# QED_2550_SOLO.net
KiCad netlist of a schematic drawn in EAGLE
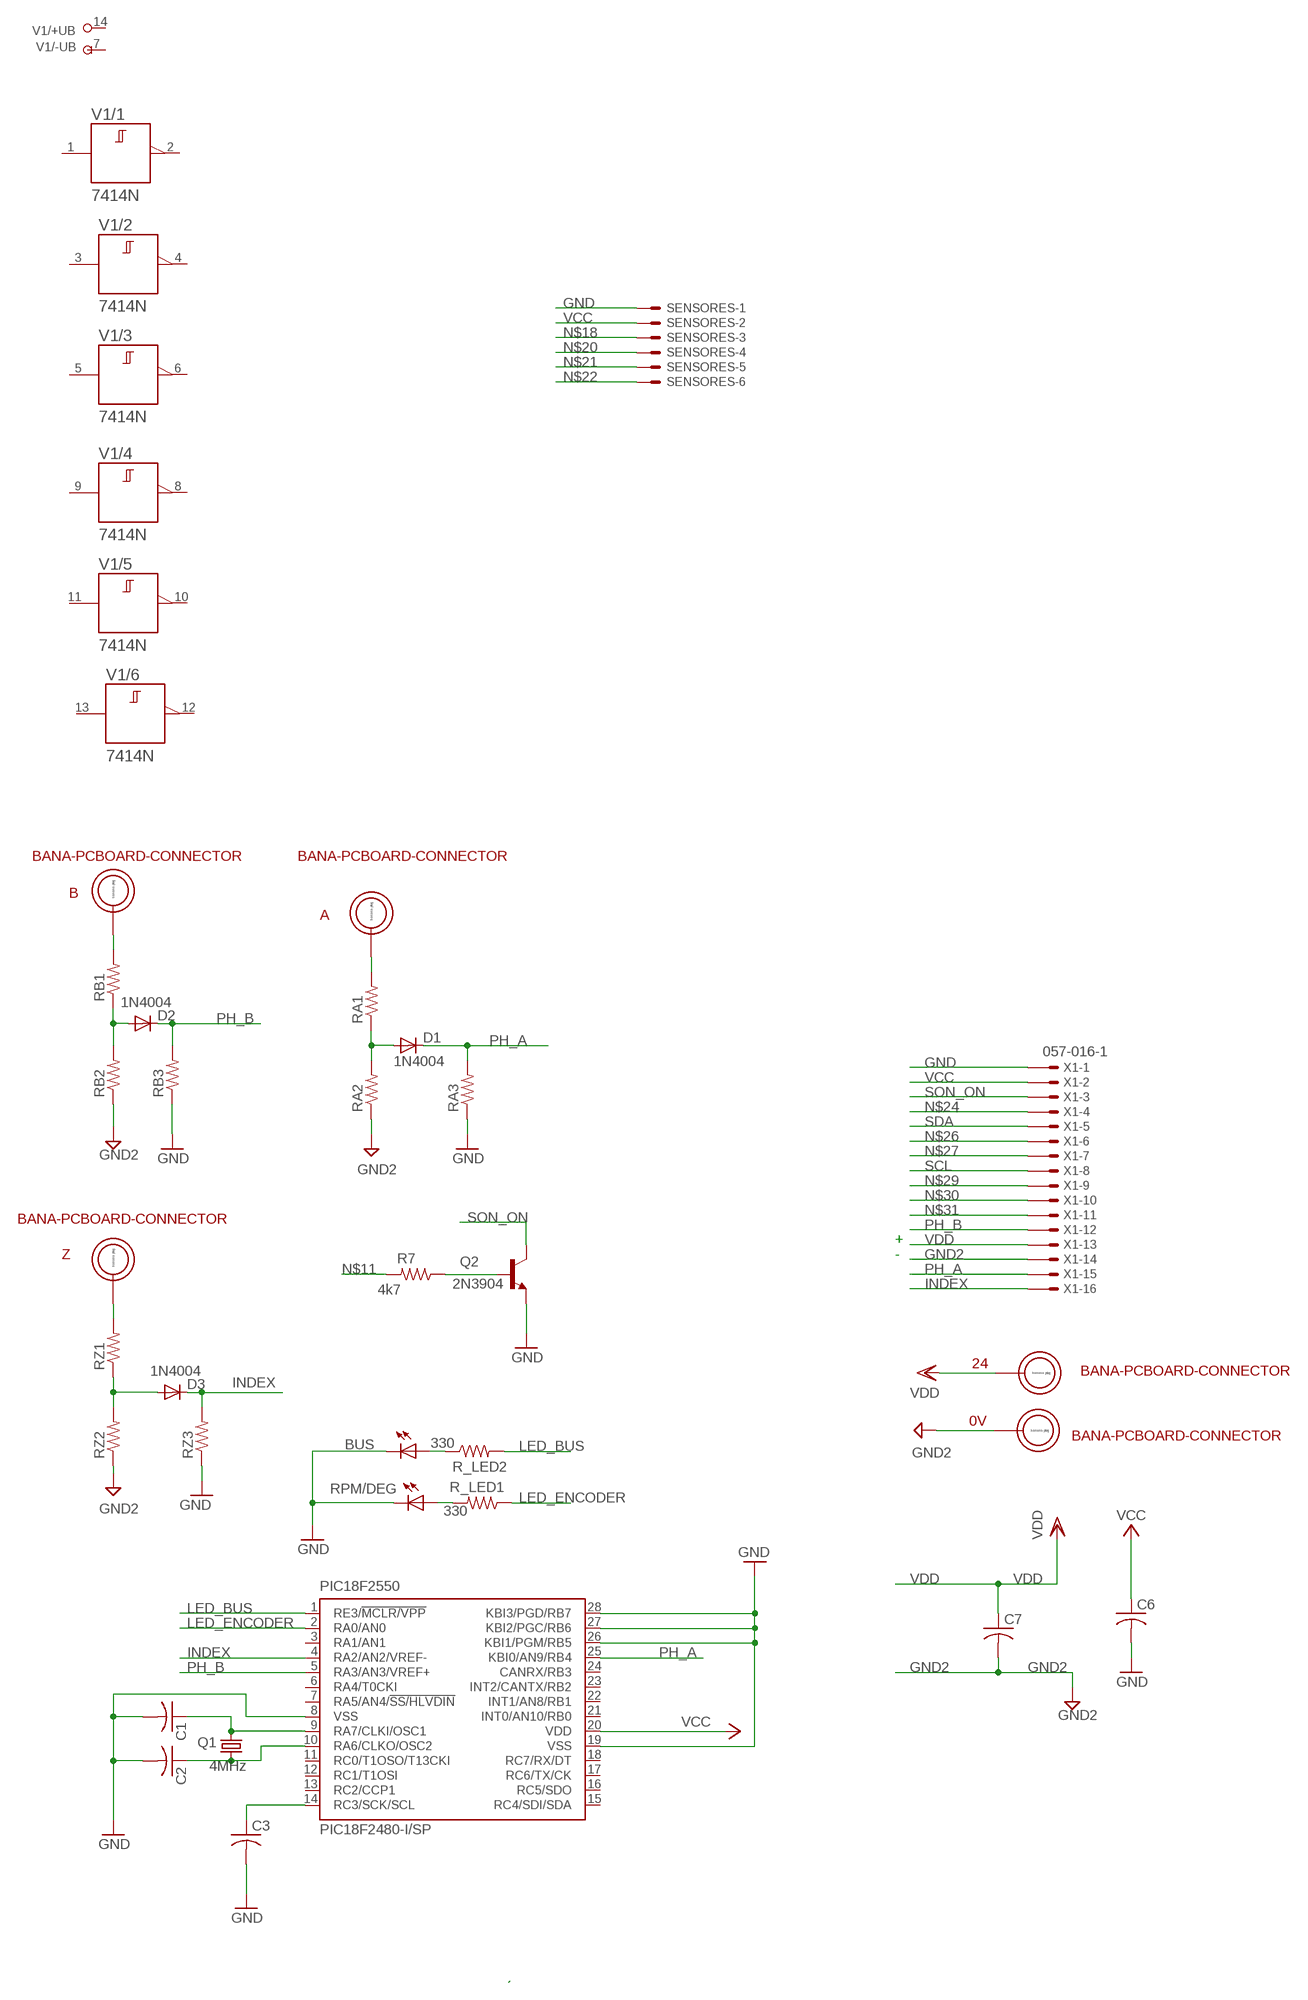
[diagram p0: schematic, sheet 1]

(export (version "E")
  (design (tool "Eeschema 10.0.6"))
  (components
    (comp (ref "0V")
      (value "BANA-PCBOARD-CONNECTOR")
      (footprint "eagle-import:BANA_PLUG")
      (libsource (lib "eagle-import") (part "BANA-PCBOARD-CONNECTOR"))
    )
    (comp (ref "24")
      (value "BANA-PCBOARD-CONNECTOR")
      (footprint "eagle-import:BANA_PLUG")
      (libsource (lib "eagle-import") (part "BANA-PCBOARD-CONNECTOR"))
    )
    (comp (ref "A")
      (value "BANA-PCBOARD-CONNECTOR")
      (footprint "eagle-import:BANA_PLUG")
      (libsource (lib "eagle-import") (part "BANA-PCBOARD-CONNECTOR"))
    )
    (comp (ref "B")
      (value "BANA-PCBOARD-CONNECTOR")
      (footprint "eagle-import:BANA_PLUG")
      (libsource (lib "eagle-import") (part "BANA-PCBOARD-CONNECTOR"))
    )
    (comp (ref "BUS")
      (value "LED5MM")
      (footprint "eagle-import:LED5MM")
      (libsource (lib "eagle-import") (part "LED5MM"))
    )
    (comp (ref "C1")
      (value "C-US025-024X044")
      (footprint "eagle-import:C025-024X044")
      (libsource (lib "eagle-import") (part "C-US025-024X044"))
    )
    (comp (ref "C2")
      (value "C-US025-024X044")
      (footprint "eagle-import:C025-024X044")
      (libsource (lib "eagle-import") (part "C-US025-024X044"))
    )
    (comp (ref "C3")
      (value "C-US025-024X044")
      (footprint "eagle-import:C025-024X044")
      (libsource (lib "eagle-import") (part "C-US025-024X044"))
    )
    (comp (ref "C6")
      (value "C-US025-030X050")
      (footprint "eagle-import:C025-030X050")
      (libsource (lib "eagle-import") (part "C-US025-030X050"))
    )
    (comp (ref "C7")
      (value "C-US025-030X050")
      (footprint "eagle-import:C025-030X050")
      (libsource (lib "eagle-import") (part "C-US025-030X050"))
    )
    (comp (ref "D1")
      (value "1N4004")
      (footprint "eagle-import:DO41-10")
      (libsource (lib "eagle-import") (part "1N4004"))
    )
    (comp (ref "D2")
      (value "1N4004")
      (footprint "eagle-import:DO41-10")
      (libsource (lib "eagle-import") (part "1N4004"))
    )
    (comp (ref "D3")
      (value "1N4004")
      (footprint "eagle-import:DO41-10")
      (libsource (lib "eagle-import") (part "1N4004"))
    )
    (comp (ref "PIC18F2550")
      (value "PIC18F2480-I/SP")
      (footprint "eagle-import:DIL28-3")
      (fields (field (name "MF") "MICROCHIP"))
      (libsource (lib "eagle-import") (part "PIC18F280-I/SP4"))
    )
    (comp (ref "Q1")
      (value "4MHz")
      (footprint "eagle-import:HC49_S")
      (libsource (lib "eagle-import") (part "CRYSTALHC49S"))
    )
    (comp (ref "Q2")
      (value "2N3904")
      (footprint "eagle-import:TO92")
      (libsource (lib "eagle-import") (part "2N3904"))
    )
    (comp (ref "R7")
      (value "4k7")
      (footprint "eagle-import:0204_7")
      (libsource (lib "eagle-import") (part "R-US_0204/7"))
    )
    (comp (ref "RA1")
      (value "R-US_0204/7")
      (footprint "eagle-import:0204_7")
      (libsource (lib "eagle-import") (part "R-US_0204/7"))
    )
    (comp (ref "RA2")
      (value "R-US_0204/7")
      (footprint "eagle-import:0204_7")
      (libsource (lib "eagle-import") (part "R-US_0204/7"))
    )
    (comp (ref "RA3")
      (value "R-US_0204/7")
      (footprint "eagle-import:0204_7")
      (libsource (lib "eagle-import") (part "R-US_0204/7"))
    )
    (comp (ref "RB1")
      (value "R-US_0204/7")
      (footprint "eagle-import:0204_7")
      (libsource (lib "eagle-import") (part "R-US_0204/7"))
    )
    (comp (ref "RB2")
      (value "R-US_0204/7")
      (footprint "eagle-import:0204_7")
      (libsource (lib "eagle-import") (part "R-US_0204/7"))
    )
    (comp (ref "RB3")
      (value "R-US_0204/7")
      (footprint "eagle-import:0204_7")
      (libsource (lib "eagle-import") (part "R-US_0204/7"))
    )
    (comp (ref "RPM/DEG")
      (value "LED5MM")
      (footprint "eagle-import:LED5MM")
      (libsource (lib "eagle-import") (part "LED5MM"))
    )
    (comp (ref "RZ1")
      (value "R-US_0204/7")
      (footprint "eagle-import:0204_7")
      (libsource (lib "eagle-import") (part "R-US_0204/7"))
    )
    (comp (ref "RZ2")
      (value "R-US_0204/7")
      (footprint "eagle-import:0204_7")
      (libsource (lib "eagle-import") (part "R-US_0204/7"))
    )
    (comp (ref "RZ3")
      (value "R-US_0204/7")
      (footprint "eagle-import:0204_7")
      (libsource (lib "eagle-import") (part "R-US_0204/7"))
    )
    (comp (ref "R_LED1")
      (value "330")
      (footprint "eagle-import:0204_7")
      (libsource (lib "eagle-import") (part "R-US_0204/7"))
    )
    (comp (ref "R_LED2")
      (value "330")
      (footprint "eagle-import:0204_7")
      (libsource (lib "eagle-import") (part "R-US_0204/7"))
    )
    (comp (ref "SENSORES")
      (value "22-23-2061")
      (footprint "eagle-import:22-23-2061")
      (fields (field (name "MF") "MOLEX"))
      (libsource (lib "eagle-import") (part "22-23-2061"))
    )
    (comp (ref "V1")
      (value "7414N")
      (footprint "eagle-import:DIL14")
      (libsource (lib "eagle-import") (part "7414N"))
    )
    (comp (ref "X1")
      (value "057-016-1")
      (footprint "eagle-import:057-016-1")
      (libsource (lib "eagle-import") (part "057-016-1"))
    )
    (comp (ref "Z")
      (value "BANA-PCBOARD-CONNECTOR")
      (footprint "eagle-import:BANA_PLUG")
      (libsource (lib "eagle-import") (part "BANA-PCBOARD-CONNECTOR"))
    )
  )
  (nets
    (net (code "1") (name "/+UB") (class "Default")
      (node (ref "V1") (pin "14") (pinfunction "+UB_14") (pintype "power_in"))
    )
    (net (code "2") (name "/-UB") (class "Default")
      (node (ref "V1") (pin "7") (pinfunction "-UB_7") (pintype "power_in"))
    )
    (net (code "3") (name "/INDEX") (class "Default")
      (node (ref "D3") (pin "C") (pinfunction "C_C") (pintype "passive"))
      (node (ref "PIC18F2550") (pin "4") (pinfunction "RA2/AN2/VREF-_4") (pintype "bidirectional"))
      (node (ref "RZ3") (pin "2") (pinfunction "2_2") (pintype "passive"))
      (node (ref "X1") (pin "16") (pinfunction "S_16") (pintype "passive"))
    )
    (net (code "4") (name "/LED_BUS") (class "Default")
      (node (ref "PIC18F2550") (pin "1") (pinfunction "RE3/~{MCLR/VPP}_1") (pintype "input"))
      (node (ref "R_LED2") (pin "2") (pinfunction "2_2") (pintype "passive"))
    )
    (net (code "5") (name "/LED_ENCODER") (class "Default")
      (node (ref "PIC18F2550") (pin "2") (pinfunction "RA0/AN0_2") (pintype "bidirectional"))
      (node (ref "R_LED1") (pin "1") (pinfunction "1_1") (pintype "passive"))
    )
    (net (code "6") (name "/N$11") (class "Default")
      (node (ref "R7") (pin "2") (pinfunction "2_2") (pintype "passive"))
    )
    (net (code "7") (name "/N$18") (class "Default")
      (node (ref "SENSORES") (pin "3") (pinfunction "S_3") (pintype "passive"))
    )
    (net (code "8") (name "/N$20") (class "Default")
      (node (ref "SENSORES") (pin "4") (pinfunction "S_4") (pintype "passive"))
    )
    (net (code "9") (name "/N$21") (class "Default")
      (node (ref "SENSORES") (pin "5") (pinfunction "S_5") (pintype "passive"))
    )
    (net (code "10") (name "/N$22") (class "Default")
      (node (ref "SENSORES") (pin "6") (pinfunction "S_6") (pintype "passive"))
    )
    (net (code "11") (name "/N$24") (class "Default")
      (node (ref "X1") (pin "4") (pinfunction "S_4") (pintype "passive"))
    )
    (net (code "12") (name "/N$26") (class "Default")
      (node (ref "X1") (pin "6") (pinfunction "S_6") (pintype "passive"))
    )
    (net (code "13") (name "/N$27") (class "Default")
      (node (ref "X1") (pin "7") (pinfunction "S_7") (pintype "passive"))
    )
    (net (code "14") (name "/N$29") (class "Default")
      (node (ref "X1") (pin "9") (pinfunction "S_9") (pintype "passive"))
    )
    (net (code "15") (name "/N$30") (class "Default")
      (node (ref "X1") (pin "10") (pinfunction "S_10") (pintype "passive"))
    )
    (net (code "16") (name "/N$31") (class "Default")
      (node (ref "X1") (pin "11") (pinfunction "S_11") (pintype "passive"))
    )
    (net (code "17") (name "/PH_A") (class "Default")
      (node (ref "D1") (pin "C") (pinfunction "C_C") (pintype "passive"))
      (node (ref "PIC18F2550") (pin "25") (pinfunction "KBI0/AN9/RB4_25") (pintype "bidirectional"))
      (node (ref "RA3") (pin "2") (pinfunction "2_2") (pintype "passive"))
      (node (ref "X1") (pin "15") (pinfunction "S_15") (pintype "passive"))
    )
    (net (code "18") (name "/PH_B") (class "Default")
      (node (ref "D2") (pin "C") (pinfunction "C_C") (pintype "passive"))
      (node (ref "PIC18F2550") (pin "5") (pinfunction "RA3/AN3/VREF+_5") (pintype "bidirectional"))
      (node (ref "RB3") (pin "2") (pinfunction "2_2") (pintype "passive"))
      (node (ref "X1") (pin "12") (pinfunction "S_12") (pintype "passive"))
    )
    (net (code "19") (name "/SCL") (class "Default")
      (node (ref "X1") (pin "8") (pinfunction "S_8") (pintype "passive"))
    )
    (net (code "20") (name "/SDA") (class "Default")
      (node (ref "X1") (pin "5") (pinfunction "S_5") (pintype "passive"))
    )
    (net (code "21") (name "/SON_ON") (class "Default")
      (node (ref "Q2") (pin "1") (pinfunction "C_1") (pintype "passive"))
      (node (ref "X1") (pin "3") (pinfunction "S_3") (pintype "passive"))
    )
    (net (code "22") (name "GND") (class "Default")
      (node (ref "BUS") (pin "K") (pinfunction "C_K") (pintype "passive"))
      (node (ref "C1") (pin "2") (pinfunction "2_2") (pintype "passive"))
      (node (ref "C2") (pin "2") (pinfunction "2_2") (pintype "passive"))
      (node (ref "C3") (pin "2") (pinfunction "2_2") (pintype "passive"))
      (node (ref "C6") (pin "2") (pinfunction "2_2") (pintype "passive"))
      (node (ref "PIC18F2550") (pin "19") (pinfunction "VSS_19") (pintype "power_in"))
      (node (ref "PIC18F2550") (pin "26") (pinfunction "KBI1/PGM/RB5_26") (pintype "bidirectional"))
      (node (ref "PIC18F2550") (pin "27") (pinfunction "KBI2/PGC/RB6_27") (pintype "bidirectional"))
      (node (ref "PIC18F2550") (pin "28") (pinfunction "KBI3/PGD/RB7_28") (pintype "bidirectional"))
      (node (ref "PIC18F2550") (pin "8") (pinfunction "VSS_8") (pintype "power_in"))
      (node (ref "Q2") (pin "3") (pinfunction "E_3") (pintype "passive"))
      (node (ref "RA3") (pin "1") (pinfunction "1_1") (pintype "passive"))
      (node (ref "RB3") (pin "1") (pinfunction "1_1") (pintype "passive"))
      (node (ref "RPM/DEG") (pin "K") (pinfunction "C_K") (pintype "passive"))
      (node (ref "RZ3") (pin "1") (pinfunction "1_1") (pintype "passive"))
      (node (ref "SENSORES") (pin "1") (pinfunction "S_1") (pintype "passive"))
      (node (ref "X1") (pin "1") (pinfunction "S_1") (pintype "passive"))
    )
    (net (code "23") (name "GND2") (class "Default")
      (node (ref "0V") (pin "P$1") (pinfunction "P$1_P$1") (pintype "bidirectional"))
      (node (ref "C7") (pin "2") (pinfunction "2_2") (pintype "passive"))
      (node (ref "RA2") (pin "1") (pinfunction "1_1") (pintype "passive"))
      (node (ref "RB2") (pin "1") (pinfunction "1_1") (pintype "passive"))
      (node (ref "RZ2") (pin "1") (pinfunction "1_1") (pintype "passive"))
      (node (ref "X1") (pin "14") (pinfunction "S_14") (pintype "passive"))
    )
    (net (code "24") (name "Net-(A-PadP$1)") (class "Default")
      (node (ref "A") (pin "P$1") (pinfunction "P$1_P$1") (pintype "bidirectional"))
      (node (ref "RA1") (pin "2") (pinfunction "2_2") (pintype "passive"))
    )
    (net (code "25") (name "Net-(B-PadP$1)") (class "Default")
      (node (ref "B") (pin "P$1") (pinfunction "P$1_P$1") (pintype "bidirectional"))
      (node (ref "RB1") (pin "2") (pinfunction "2_2") (pintype "passive"))
    )
    (net (code "26") (name "Net-(BUS-PadA)") (class "Default")
      (node (ref "BUS") (pin "A") (pinfunction "A_A") (pintype "passive"))
      (node (ref "R_LED2") (pin "1") (pinfunction "1_1") (pintype "passive"))
    )
    (net (code "27") (name "Net-(D1-PadA)") (class "Default")
      (node (ref "D1") (pin "A") (pinfunction "A_A") (pintype "passive"))
      (node (ref "RA1") (pin "1") (pinfunction "1_1") (pintype "passive"))
      (node (ref "RA2") (pin "2") (pinfunction "2_2") (pintype "passive"))
    )
    (net (code "28") (name "Net-(D2-PadA)") (class "Default")
      (node (ref "D2") (pin "A") (pinfunction "A_A") (pintype "passive"))
      (node (ref "RB1") (pin "1") (pinfunction "1_1") (pintype "passive"))
      (node (ref "RB2") (pin "2") (pinfunction "2_2") (pintype "passive"))
    )
    (net (code "29") (name "Net-(D3-PadA)") (class "Default")
      (node (ref "D3") (pin "A") (pinfunction "A_A") (pintype "passive"))
      (node (ref "RZ1") (pin "1") (pinfunction "1_1") (pintype "passive"))
      (node (ref "RZ2") (pin "2") (pinfunction "2_2") (pintype "passive"))
    )
    (net (code "30") (name "Net-(PIC18F2550-RA6{slash}CLKO{slash}OSC2)") (class "Default")
      (node (ref "C2") (pin "1") (pinfunction "1_1") (pintype "passive"))
      (node (ref "PIC18F2550") (pin "10") (pinfunction "RA6/CLKO/OSC2_10") (pintype "output"))
      (node (ref "Q1") (pin "1") (pinfunction "1_1") (pintype "passive"))
    )
    (net (code "31") (name "Net-(PIC18F2550-RA7{slash}CLKI{slash}OSC1)") (class "Default")
      (node (ref "C1") (pin "1") (pinfunction "1_1") (pintype "passive"))
      (node (ref "PIC18F2550") (pin "9") (pinfunction "RA7/CLKI/OSC1_9") (pintype "input"))
      (node (ref "Q1") (pin "2") (pinfunction "2_2") (pintype "passive"))
    )
    (net (code "32") (name "Net-(PIC18F2550-RC3{slash}SCK{slash}SCL)") (class "Default")
      (node (ref "C3") (pin "1") (pinfunction "1_1") (pintype "passive"))
      (node (ref "PIC18F2550") (pin "14") (pinfunction "RC3/SCK/SCL_14") (pintype "bidirectional"))
    )
    (net (code "33") (name "Net-(Q2-B)") (class "Default")
      (node (ref "Q2") (pin "2") (pinfunction "B_2") (pintype "passive"))
      (node (ref "R7") (pin "1") (pinfunction "1_1") (pintype "passive"))
    )
    (net (code "34") (name "Net-(RPM/DEG-PadA)") (class "Default")
      (node (ref "RPM/DEG") (pin "A") (pinfunction "A_A") (pintype "passive"))
      (node (ref "R_LED1") (pin "2") (pinfunction "2_2") (pintype "passive"))
    )
    (net (code "35") (name "Net-(RZ1-Pad2)") (class "Default")
      (node (ref "RZ1") (pin "2") (pinfunction "2_2") (pintype "passive"))
      (node (ref "Z") (pin "P$1") (pinfunction "P$1_P$1") (pintype "bidirectional"))
    )
    (net (code "36") (name "VCC") (class "Default")
      (node (ref "C6") (pin "1") (pinfunction "1_1") (pintype "passive"))
      (node (ref "PIC18F2550") (pin "20") (pinfunction "VDD_20") (pintype "power_in"))
      (node (ref "SENSORES") (pin "2") (pinfunction "S_2") (pintype "passive"))
      (node (ref "X1") (pin "2") (pinfunction "S_2") (pintype "passive"))
    )
    (net (code "37") (name "VDD") (class "Default")
      (node (ref "24") (pin "P$1") (pinfunction "P$1_P$1") (pintype "bidirectional"))
      (node (ref "C7") (pin "1") (pinfunction "1_1") (pintype "passive"))
      (node (ref "X1") (pin "13") (pinfunction "S_13") (pintype "passive"))
    )
    (net (code "38") (name "unconnected-(PIC18F2550-CANRX{slash}RB3-Pad24)") (class "Default")
      (node (ref "PIC18F2550") (pin "24") (pinfunction "CANRX/RB3_24") (pintype "bidirectional"))
    )
    (net (code "39") (name "unconnected-(PIC18F2550-INT0{slash}AN10{slash}RB0-Pad21)") (class "Default")
      (node (ref "PIC18F2550") (pin "21") (pinfunction "INT0/AN10/RB0_21") (pintype "bidirectional"))
    )
    (net (code "40") (name "unconnected-(PIC18F2550-INT1{slash}AN8{slash}RB1-Pad22)") (class "Default")
      (node (ref "PIC18F2550") (pin "22") (pinfunction "INT1/AN8/RB1_22") (pintype "bidirectional"))
    )
    (net (code "41") (name "unconnected-(PIC18F2550-INT2{slash}CANTX{slash}RB2-Pad23)") (class "Default")
      (node (ref "PIC18F2550") (pin "23") (pinfunction "INT2/CANTX/RB2_23") (pintype "bidirectional"))
    )
    (net (code "42") (name "unconnected-(PIC18F2550-RA1{slash}AN1-Pad3)") (class "Default")
      (node (ref "PIC18F2550") (pin "3") (pinfunction "RA1/AN1_3") (pintype "bidirectional"))
    )
    (net (code "43") (name "unconnected-(PIC18F2550-RA4{slash}T0CKI-Pad6)") (class "Default")
      (node (ref "PIC18F2550") (pin "6") (pinfunction "RA4/T0CKI_6") (pintype "bidirectional"))
    )
    (net (code "44") (name "unconnected-(PIC18F2550-RA5{slash}AN4{slash}~{SS{slash}HLVDIN}-Pad7)") (class "Default")
      (node (ref "PIC18F2550") (pin "7") (pinfunction "RA5/AN4/~{SS/HLVDIN}_7") (pintype "bidirectional"))
    )
    (net (code "45") (name "unconnected-(PIC18F2550-RC0{slash}T1OSO{slash}T13CKI-Pad11)") (class "Default")
      (node (ref "PIC18F2550") (pin "11") (pinfunction "RC0/T1OSO/T13CKI_11") (pintype "bidirectional"))
    )
    (net (code "46") (name "unconnected-(PIC18F2550-RC1{slash}T1OSI-Pad12)") (class "Default")
      (node (ref "PIC18F2550") (pin "12") (pinfunction "RC1/T1OSI_12") (pintype "bidirectional"))
    )
    (net (code "47") (name "unconnected-(PIC18F2550-RC2{slash}CCP1-Pad13)") (class "Default")
      (node (ref "PIC18F2550") (pin "13") (pinfunction "RC2/CCP1_13") (pintype "bidirectional"))
    )
    (net (code "48") (name "unconnected-(PIC18F2550-RC4{slash}SDI{slash}SDA-Pad15)") (class "Default")
      (node (ref "PIC18F2550") (pin "15") (pinfunction "RC4/SDI/SDA_15") (pintype "bidirectional"))
    )
    (net (code "49") (name "unconnected-(PIC18F2550-RC5{slash}SDO-Pad16)") (class "Default")
      (node (ref "PIC18F2550") (pin "16") (pinfunction "RC5/SDO_16") (pintype "bidirectional"))
    )
    (net (code "50") (name "unconnected-(PIC18F2550-RC6{slash}TX{slash}CK-Pad17)") (class "Default")
      (node (ref "PIC18F2550") (pin "17") (pinfunction "RC6/TX/CK_17") (pintype "bidirectional"))
    )
    (net (code "51") (name "unconnected-(PIC18F2550-RC7{slash}RX{slash}DT-Pad18)") (class "Default")
      (node (ref "PIC18F2550") (pin "18") (pinfunction "RC7/RX/DT_18") (pintype "bidirectional"))
    )
    (net (code "52") (name "unconnected-(V1C-A-Pad1)") (class "Default")
      (node (ref "V1") (pin "1") (pinfunction "A_1") (pintype "input"))
    )
    (net (code "53") (name "unconnected-(V1C-Y-Pad2)") (class "Default")
      (node (ref "V1") (pin "2") (pinfunction "Y_2") (pintype "output"))
    )
    (net (code "54") (name "unconnected-(V1D-A-Pad3)") (class "Default")
      (node (ref "V1") (pin "3") (pinfunction "A_3") (pintype "input"))
    )
    (net (code "55") (name "unconnected-(V1D-Y-Pad4)") (class "Default")
      (node (ref "V1") (pin "4") (pinfunction "Y_4") (pintype "output"))
    )
    (net (code "56") (name "unconnected-(V1E-A-Pad5)") (class "Default")
      (node (ref "V1") (pin "5") (pinfunction "A_5") (pintype "input"))
    )
    (net (code "57") (name "unconnected-(V1E-Y-Pad6)") (class "Default")
      (node (ref "V1") (pin "6") (pinfunction "Y_6") (pintype "output"))
    )
    (net (code "58") (name "unconnected-(V1F-A-Pad9)") (class "Default")
      (node (ref "V1") (pin "9") (pinfunction "A_9") (pintype "input"))
    )
    (net (code "59") (name "unconnected-(V1F-Y-Pad8)") (class "Default")
      (node (ref "V1") (pin "8") (pinfunction "Y_8") (pintype "output"))
    )
    (net (code "60") (name "unconnected-(V1G-A-Pad11)") (class "Default")
      (node (ref "V1") (pin "11") (pinfunction "A_11") (pintype "input"))
    )
    (net (code "61") (name "unconnected-(V1G-Y-Pad10)") (class "Default")
      (node (ref "V1") (pin "10") (pinfunction "Y_10") (pintype "output"))
    )
    (net (code "62") (name "unconnected-(V1H-A-Pad13)") (class "Default")
      (node (ref "V1") (pin "13") (pinfunction "A_13") (pintype "input"))
    )
    (net (code "63") (name "unconnected-(V1H-Y-Pad12)") (class "Default")
      (node (ref "V1") (pin "12") (pinfunction "Y_12") (pintype "output"))
    )
  )
)
